# Escorna_CPU_2_40.net
KiCad netlist of a schematic drawn in EAGLE
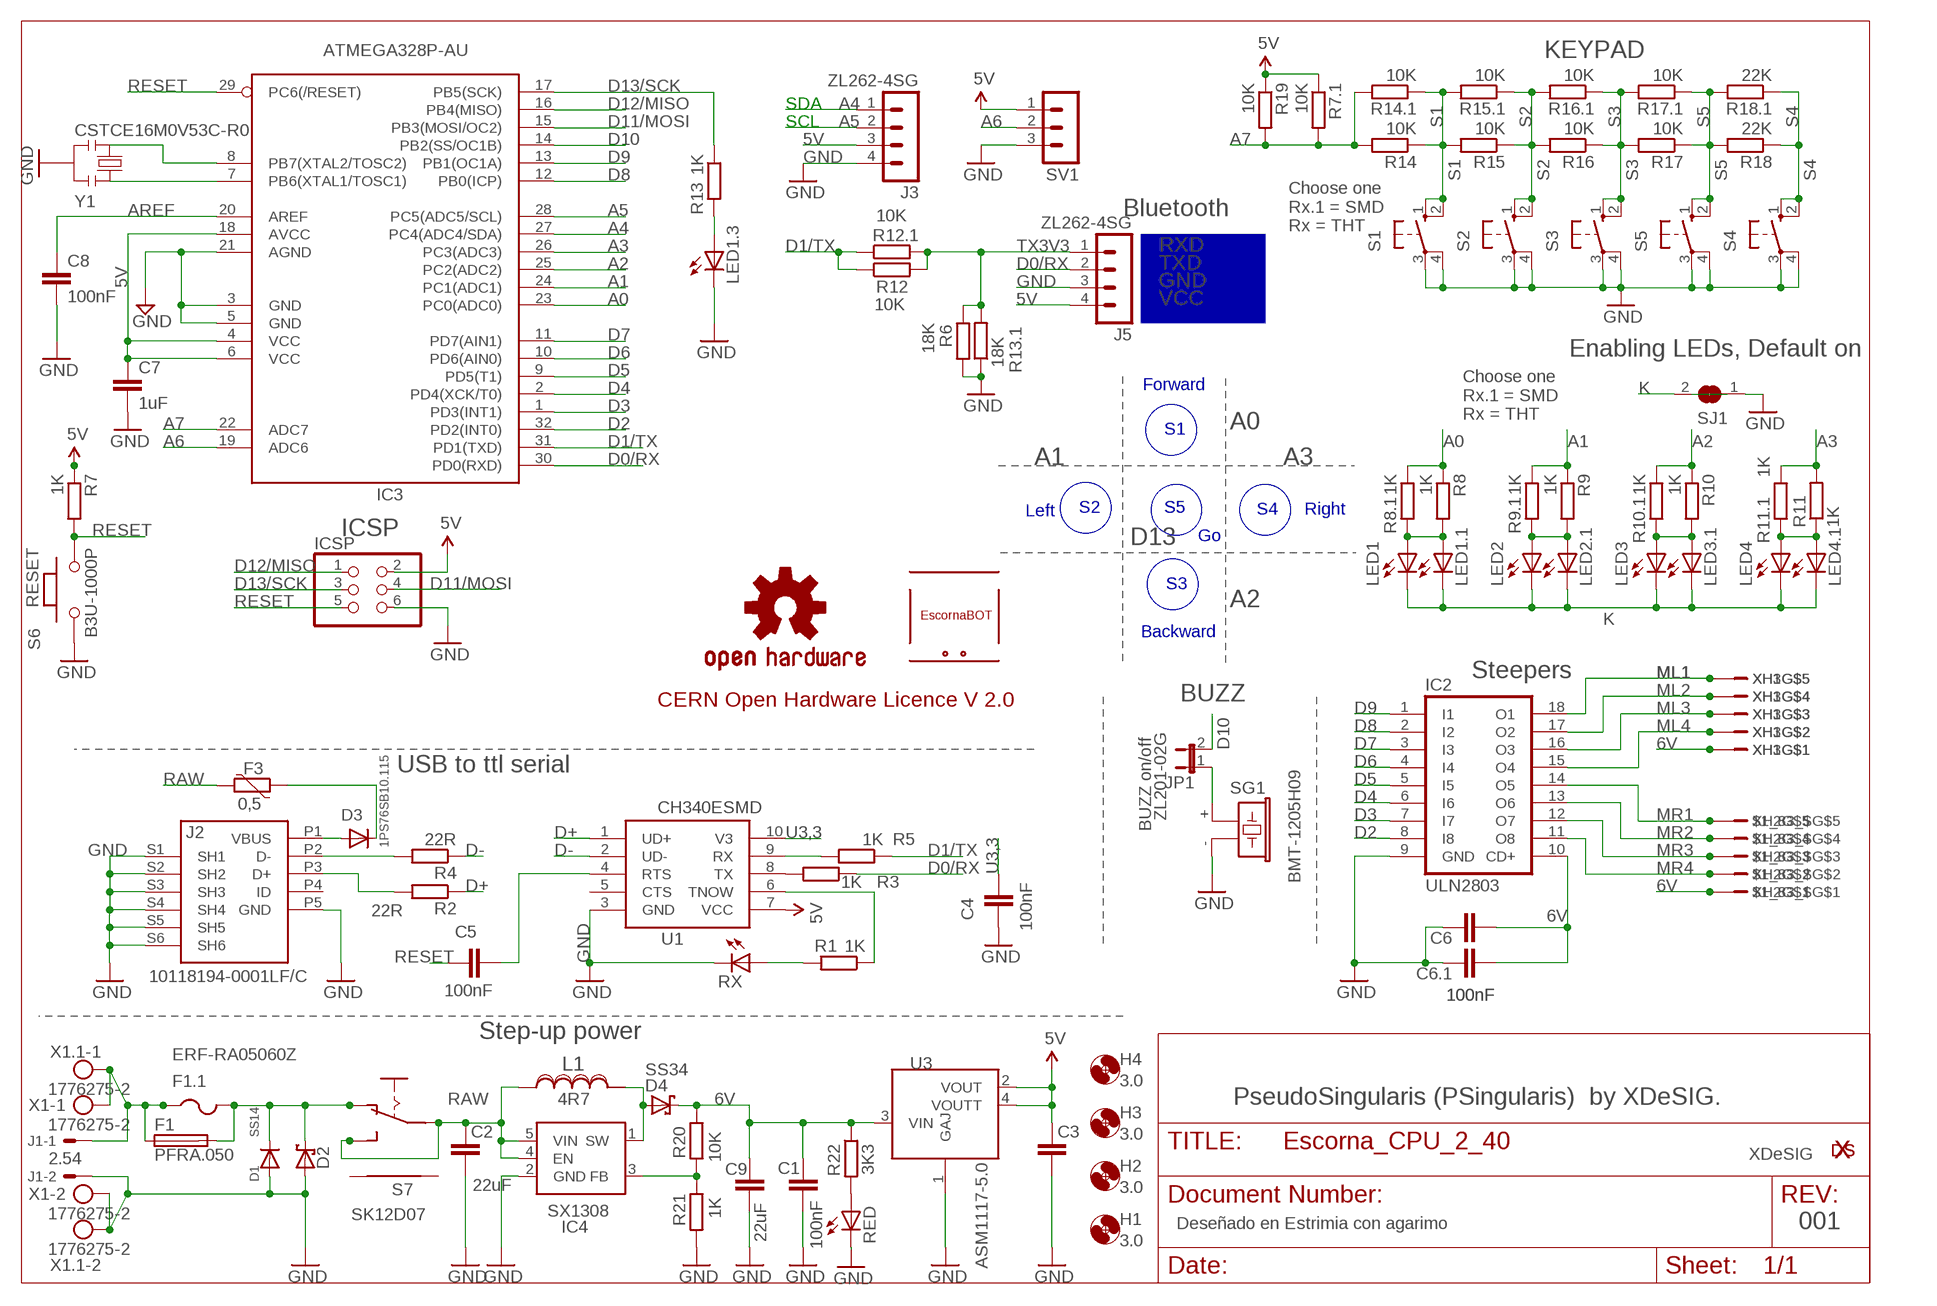
[diagram p0: schematic, sheet 1]

(export (version "E")
  (design (tool "Eeschema 10.0.6"))
  (components
    (comp (ref "$1_82_$")
      (value "XDESIG_XDESIG21")
      (footprint "eagle-import:XDESIG_XDESIG")
      (libsource (lib "eagle-import") (part "XDESIG_XDESIG21"))
    )
    (comp (ref "$1_83_$")
      (value "B5B-XH-A")
      (footprint "eagle-import:B5B-XH-A")
      (libsource (lib "eagle-import") (part "B5B-XH-A"))
    )
    (comp (ref "C1")
      (value "100nF")
      (footprint "eagle-import:C0603-ROUND")
      (fields (field (name "PART_NUMBER") "cl10b104kbnc"))
      (libsource (lib "eagle-import") (part "0015_100NF_0603"))
    )
    (comp (ref "C2")
      (value "22uF")
      (footprint "eagle-import:C1206K")
      (libsource (lib "eagle-import") (part "C-EUC1206K"))
    )
    (comp (ref "C3")
      (value "10uF")
      (footprint "eagle-import:C1206K")
      (libsource (lib "eagle-import") (part "C-EUC1206K"))
    )
    (comp (ref "C4")
      (value "100nF")
      (footprint "eagle-import:C0603-ROUND")
      (fields (field (name "PART_NUMBER") "cl10b104kbnc"))
      (libsource (lib "eagle-import") (part "0015_100NF_0603"))
    )
    (comp (ref "C5")
      (value "100nF")
      (footprint "eagle-import:C0603-ROUND")
      (fields (field (name "PART_NUMBER") "cl10b104kbnc"))
      (libsource (lib "eagle-import") (part "0015_100NF_0603"))
    )
    (comp (ref "C6")
      (value "100nF")
      (footprint "eagle-import:C025-024X044")
      (libsource (lib "eagle-import") (part "C-EU025-024X044"))
    )
    (comp (ref "C6.1")
      (value "100nF")
      (footprint "eagle-import:C0603K")
      (libsource (lib "eagle-import") (part "C-EUC0603K"))
    )
    (comp (ref "C7")
      (value "1uF")
      (footprint "eagle-import:C0603-ROUND")
      (fields (field (name "PART_NUMBER") "1uF_0603/GRM188R61E105KA12D"))
      (libsource (lib "eagle-import") (part "0006_1UF_0603/GRM188R61E105KA12D"))
    )
    (comp (ref "C8")
      (value "100nF")
      (footprint "eagle-import:C0603-ROUND")
      (fields (field (name "PART_NUMBER") "cl10b104kbnc"))
      (libsource (lib "eagle-import") (part "0015_100NF_0603"))
    )
    (comp (ref "C9")
      (value "22uF")
      (footprint "eagle-import:C1206K")
      (libsource (lib "eagle-import") (part "C-EUC1206K"))
    )
    (comp (ref "D1")
      (value "SS14")
      (footprint "eagle-import:SMADIODE")
      (libsource (lib "eagle-import") (part "DIODESMA"))
    )
    (comp (ref "D2")
      (value "1N5817")
      (footprint "eagle-import:DO41-10")
      (libsource (lib "eagle-import") (part "P4KEXX"))
    )
    (comp (ref "D3")
      (value "1PS76SB10.115")
      (footprint "eagle-import:SOD-323F")
      (libsource (lib "eagle-import") (part "DIODESOD-323F"))
    )
    (comp (ref "D4")
      (value "SS34")
      (footprint "eagle-import:DIODE_SMA")
      (libsource (lib "eagle-import") (part "DIODE_SCHOTTKY-DIODESMA"))
    )
    (comp (ref "ESC")
      (value "ESCORNABOT")
      (footprint "eagle-import:ESCORNA_PEQUE")
      (libsource (lib "eagle-import") (part "ESCORNABOT"))
    )
    (comp (ref "F1")
      (value "PFRA.050")
      (footprint "eagle-import:TE5")
      (libsource (lib "eagle-import") (part "FUSETE5"))
    )
    (comp (ref "F1.1")
      (value "ERF-RA05060Z")
      (footprint "eagle-import:R1206")
      (libsource (lib "eagle-import") (part "PTCFUSE-1206"))
    )
    (comp (ref "F3")
      (value "0,5")
      (footprint "eagle-import:R1206")
      (libsource (lib "eagle-import") (part "PTC1206L"))
    )
    (comp (ref "H1")
      (value "3.0")
      (footprint "eagle-import:3,0")
      (libsource (lib "eagle-import") (part "MOUNT-HOLE3.0"))
    )
    (comp (ref "H2")
      (value "3.0")
      (footprint "eagle-import:3,0")
      (libsource (lib "eagle-import") (part "MOUNT-HOLE3.0"))
    )
    (comp (ref "H3")
      (value "3.0")
      (footprint "eagle-import:3,0")
      (libsource (lib "eagle-import") (part "MOUNT-HOLE3.0"))
    )
    (comp (ref "H4")
      (value "3.0")
      (footprint "eagle-import:3,0")
      (libsource (lib "eagle-import") (part "MOUNT-HOLE3.0"))
    )
    (comp (ref "IC2")
      (value "ULN2803")
      (footprint "eagle-import:DIL18")
      (libsource (lib "eagle-import") (part "ULN2803A"))
    )
    (comp (ref "IC3")
      (value "ATMEGA328P-AU")
      (footprint "eagle-import:TQFP32-08")
      (libsource (lib "eagle-import") (part "0265_ATMEGA328P-AU"))
    )
    (comp (ref "IC4")
      (value "SX1308")
      (footprint "eagle-import:SOT23-6")
      (libsource (lib "eagle-import") (part "SX1308"))
    )
    (comp (ref "ICSP")
      (value "0114_PH254-203DF118A00V")
      (footprint "eagle-import:2X03")
      (fields (field (name "PART_NUMBER") "PH254-203DF118A00V"))
      (libsource (lib "eagle-import") (part "0114_PH254-203DF118A00V"))
    )
    (comp (ref "J1")
      (value "2.54")
      (footprint "eagle-import:6410-02")
      (libsource (lib "eagle-import") (part "22-?-0227-2021"))
    )
    (comp (ref "J2")
      (value "10118194-0001LF/C")
      (footprint "eagle-import:SMARTPRJ_CON2_USB_MICRO_B_AT")
      (libsource (lib "eagle-import") (part "SMARTPRJ_MYCON2_USB-MINI-B"))
    )
    (comp (ref "J3")
      (value "ZL262-4SG")
      (footprint "eagle-import:MA04-1")
      (libsource (lib "eagle-import") (part "MA04-1"))
    )
    (comp (ref "J5")
      (value "ZL262-4SG")
      (footprint "eagle-import:MA04-1")
      (libsource (lib "eagle-import") (part "MA04-1"))
    )
    (comp (ref "JP1")
      (value "ZL201-02G")
      (footprint "eagle-import:JP1")
      (libsource (lib "eagle-import") (part "JP1E"))
    )
    (comp (ref "L1")
      (value "4R7")
      (footprint "eagle-import:SRN6045")
      (fields (field (name "MF") "Bourns") (field (name "MP") "SRN6045-330M"))
      (libsource (lib "eagle-import") (part "SRN6045-330M6045"))
    )
    (comp (ref "LED1")
      (value "LED3MM")
      (footprint "eagle-import:LED3MM")
      (libsource (lib "eagle-import") (part "LED3MM"))
    )
    (comp (ref "LED1.1")
      (value "LEDCHIPLED_0603")
      (footprint "eagle-import:CHIPLED_0603")
      (libsource (lib "eagle-import") (part "LEDCHIPLED_0603"))
    )
    (comp (ref "LED1.3")
      (value "LEDCHIPLED_0603")
      (footprint "eagle-import:CHIPLED_0603")
      (libsource (lib "eagle-import") (part "LEDCHIPLED_0603"))
    )
    (comp (ref "LED2")
      (value "LED3MM")
      (footprint "eagle-import:LED3MM")
      (libsource (lib "eagle-import") (part "LED3MM"))
    )
    (comp (ref "LED2.1")
      (value "LEDCHIPLED_0603")
      (footprint "eagle-import:CHIPLED_0603")
      (libsource (lib "eagle-import") (part "LEDCHIPLED_0603"))
    )
    (comp (ref "LED3")
      (value "LED3MM")
      (footprint "eagle-import:LED3MM")
      (libsource (lib "eagle-import") (part "LED3MM"))
    )
    (comp (ref "LED3.1")
      (value "LEDCHIPLED_0603")
      (footprint "eagle-import:CHIPLED_0603")
      (libsource (lib "eagle-import") (part "LEDCHIPLED_0603"))
    )
    (comp (ref "LED4")
      (value "LED3MM")
      (footprint "eagle-import:LED3MM")
      (libsource (lib "eagle-import") (part "LED3MM"))
    )
    (comp (ref "LED4.1")
      (value "LEDCHIPLED_0603")
      (footprint "eagle-import:CHIPLED_0603")
      (libsource (lib "eagle-import") (part "LEDCHIPLED_0603"))
    )
    (comp (ref "LOGO2")
      (value "OSHW-LOGOL")
      (footprint "eagle-import:ESCORNA_LBRESCORNA_CPU_2_10_SPARKFUN-AESTHETICS_OSHW-LOGO-L")
      (libsource (lib "eagle-import") (part "OSHW-LOGOL"))
    )
    (comp (ref "R1")
      (value "1K")
      (footprint "eagle-import:R0603")
      (libsource (lib "eagle-import") (part "R-EU_R0603"))
    )
    (comp (ref "R2")
      (value "22R")
      (footprint "eagle-import:R0603")
      (libsource (lib "eagle-import") (part "R-EU_R0603"))
    )
    (comp (ref "R3")
      (value "1K")
      (footprint "eagle-import:R0603")
      (libsource (lib "eagle-import") (part "R-EU_R0603"))
    )
    (comp (ref "R4")
      (value "22R")
      (footprint "eagle-import:R0603")
      (libsource (lib "eagle-import") (part "R-EU_R0603"))
    )
    (comp (ref "R5")
      (value "1K")
      (footprint "eagle-import:R0603")
      (libsource (lib "eagle-import") (part "R-EU_R0603"))
    )
    (comp (ref "R6")
      (value "18K")
      (footprint "eagle-import:0204_7")
      (libsource (lib "eagle-import") (part "R-EU_0204/7"))
    )
    (comp (ref "R7")
      (value "1K")
      (footprint "eagle-import:R0603")
      (libsource (lib "eagle-import") (part "R-EU_R0603"))
    )
    (comp (ref "R7.1")
      (value "10K")
      (footprint "eagle-import:R0603")
      (libsource (lib "eagle-import") (part "R-EU_R0603"))
    )
    (comp (ref "R8")
      (value "1K")
      (footprint "eagle-import:0204_7")
      (libsource (lib "eagle-import") (part "R-EU_0204/7"))
    )
    (comp (ref "R8.1")
      (value "1K")
      (footprint "eagle-import:R0603")
      (libsource (lib "eagle-import") (part "R-EU_R0603"))
    )
    (comp (ref "R9")
      (value "1K")
      (footprint "eagle-import:0204_7")
      (libsource (lib "eagle-import") (part "R-EU_0204/7"))
    )
    (comp (ref "R9.1")
      (value "1K")
      (footprint "eagle-import:R0603")
      (libsource (lib "eagle-import") (part "R-EU_R0603"))
    )
    (comp (ref "R10")
      (value "1K")
      (footprint "eagle-import:0204_7")
      (libsource (lib "eagle-import") (part "R-EU_0204/7"))
    )
    (comp (ref "R10.1")
      (value "1K")
      (footprint "eagle-import:R0603")
      (libsource (lib "eagle-import") (part "R-EU_R0603"))
    )
    (comp (ref "R11")
      (value "1K")
      (footprint "eagle-import:0204_7")
      (libsource (lib "eagle-import") (part "R-EU_0204/7"))
    )
    (comp (ref "R11.1")
      (value "1K")
      (footprint "eagle-import:R0603")
      (libsource (lib "eagle-import") (part "R-EU_R0603"))
    )
    (comp (ref "R12")
      (value "10K")
      (footprint "eagle-import:0204_7")
      (libsource (lib "eagle-import") (part "R-EU_0204/7"))
    )
    (comp (ref "R12.1")
      (value "10K")
      (footprint "eagle-import:R0603")
      (libsource (lib "eagle-import") (part "R-EU_R0603"))
    )
    (comp (ref "R13")
      (value "1K")
      (footprint "eagle-import:R0603")
      (libsource (lib "eagle-import") (part "R-EU_R0603"))
    )
    (comp (ref "R13.1")
      (value "18K")
      (footprint "eagle-import:R0603")
      (libsource (lib "eagle-import") (part "R-EU_R0603"))
    )
    (comp (ref "R14")
      (value "10K")
      (footprint "eagle-import:0204_7")
      (libsource (lib "eagle-import") (part "R-EU_0204/7"))
    )
    (comp (ref "R14.1")
      (value "10K")
      (footprint "eagle-import:R0603")
      (libsource (lib "eagle-import") (part "R-EU_R0603"))
    )
    (comp (ref "R15")
      (value "10K")
      (footprint "eagle-import:0204_7")
      (libsource (lib "eagle-import") (part "R-EU_0204/7"))
    )
    (comp (ref "R15.1")
      (value "10K")
      (footprint "eagle-import:R0603")
      (libsource (lib "eagle-import") (part "R-EU_R0603"))
    )
    (comp (ref "R16")
      (value "10K")
      (footprint "eagle-import:0204_7")
      (libsource (lib "eagle-import") (part "R-EU_0204/7"))
    )
    (comp (ref "R16.1")
      (value "10K")
      (footprint "eagle-import:R0603")
      (libsource (lib "eagle-import") (part "R-EU_R0603"))
    )
    (comp (ref "R17")
      (value "10K")
      (footprint "eagle-import:0204_7")
      (libsource (lib "eagle-import") (part "R-EU_0204/7"))
    )
    (comp (ref "R17.1")
      (value "10K")
      (footprint "eagle-import:R0603")
      (libsource (lib "eagle-import") (part "R-EU_R0603"))
    )
    (comp (ref "R18")
      (value "22K")
      (footprint "eagle-import:0204_7")
      (libsource (lib "eagle-import") (part "R-EU_0204/7"))
    )
    (comp (ref "R18.1")
      (value "22K")
      (footprint "eagle-import:R0603")
      (libsource (lib "eagle-import") (part "R-EU_R0603"))
    )
    (comp (ref "R19")
      (value "10K")
      (footprint "eagle-import:0204_7")
      (libsource (lib "eagle-import") (part "R-EU_0204/7"))
    )
    (comp (ref "R20")
      (value "10K")
      (footprint "eagle-import:R0603")
      (libsource (lib "eagle-import") (part "R-EU_R0603"))
    )
    (comp (ref "R21")
      (value "1K")
      (footprint "eagle-import:R0603")
      (libsource (lib "eagle-import") (part "R-EU_R0603"))
    )
    (comp (ref "R22")
      (value "3K3")
      (footprint "eagle-import:R0603")
      (libsource (lib "eagle-import") (part "R-EU_R0603"))
    )
    (comp (ref "RED")
      (value "LEDCHIPLED_0603")
      (footprint "eagle-import:CHIPLED_0603")
      (libsource (lib "eagle-import") (part "LEDCHIPLED_0603"))
    )
    (comp (ref "RX")
      (value "LEDCHIPLED_0603")
      (footprint "eagle-import:CHIPLED_0603")
      (libsource (lib "eagle-import") (part "LEDCHIPLED_0603"))
    )
    (comp (ref "S1")
      (value "40-XX")
      (footprint "eagle-import:B3F-40")
      (fields (field (name "MF") "OMRON COMPONENTS USA") (field (name "MPN") "B3F-4000"))
      (libsource (lib "eagle-import") (part "40-XX"))
    )
    (comp (ref "S2")
      (value "40-XX")
      (footprint "eagle-import:B3F-40")
      (fields (field (name "MF") "OMRON COMPONENTS USA") (field (name "MPN") "B3F-4000"))
      (libsource (lib "eagle-import") (part "40-XX"))
    )
    (comp (ref "S3")
      (value "40-XX")
      (footprint "eagle-import:B3F-40")
      (fields (field (name "MF") "OMRON COMPONENTS USA") (field (name "MPN") "B3F-4000"))
      (libsource (lib "eagle-import") (part "40-XX"))
    )
    (comp (ref "S4")
      (value "40-XX")
      (footprint "eagle-import:B3F-40")
      (fields (field (name "MF") "OMRON COMPONENTS USA") (field (name "MPN") "B3F-4000"))
      (libsource (lib "eagle-import") (part "40-XX"))
    )
    (comp (ref "S5")
      (value "40-XX")
      (footprint "eagle-import:B3F-40")
      (fields (field (name "MF") "OMRON COMPONENTS USA") (field (name "MPN") "B3F-4000"))
      (libsource (lib "eagle-import") (part "40-XX"))
    )
    (comp (ref "S6")
      (value "B3U-1000P")
      (footprint "eagle-import:SMD_157SW")
      (fields (field (name "PART_NUMBER") "IT-1185AP1C-160G-G_T&R"))
      (libsource (lib "eagle-import") (part "0173_IT-1185AP1C-160G-G_T&R"))
    )
    (comp (ref "S7")
      (value "SK12D07")
      (footprint "eagle-import:ESCORNA_SK-12D07")
      (libsource (lib "eagle-import") (part "ESCORNA_SK12F14D"))
    )
    (comp (ref "SG1")
      (value "BMT-1205H09")
      (footprint "eagle-import:F_CM12P")
      (libsource (lib "eagle-import") (part "F/CM12P"))
    )
    (comp (ref "SJ1") (value "SJ") (footprint "eagle-import:SJ") (libsource (lib "eagle-import") (part "SJ")))
    (comp (ref "SV1")
      (value "MA03-1")
      (footprint "eagle-import:MA03-1")
      (libsource (lib "eagle-import") (part "MA03-1"))
    )
    (comp (ref "U1")
      (value "CH340ESMD")
      (footprint "eagle-import:MSOP10")
      (fields (field (name "MF") "WCH") (field (name "MP") "CH340E"))
      (libsource (lib "eagle-import") (part "CH340ESMD"))
    )
    (comp (ref "U3")
      (value "ASM1117-5.0")
      (footprint "eagle-import:SOT223")
      (libsource (lib "eagle-import") (part "ASM1117-3.3"))
    )
    (comp (ref "X1")
      (value "1776275-2")
      (footprint "eagle-import:AK550_2")
      (libsource (lib "eagle-import") (part "AK550/2"))
    )
    (comp (ref "X1.1")
      (value "1776275-2")
      (footprint "eagle-import:AK550_2")
      (fields (field (name "OC_FARNELL") "unknown") (field (name "OC_NEWARK") "unknown"))
      (libsource (lib "eagle-import") (part "AK550/2"))
    )
    (comp (ref "XDS2")
      (value "XDESIG")
      (footprint "eagle-import:XDESIG_CU_2")
      (libsource (lib "eagle-import") (part "XDESIG"))
    )
    (comp (ref "XH1")
      (value "B5B-XH-A")
      (footprint "eagle-import:B5B-XH-A")
      (libsource (lib "eagle-import") (part "B5B-XH-A"))
    )
    (comp (ref "XH2")
      (value "B5B-XH-A")
      (footprint "eagle-import:B5B-XH-A")
      (libsource (lib "eagle-import") (part "B5B-XH-A"))
    )
    (comp (ref "XH3")
      (value "B5B-XH-A")
      (footprint "eagle-import:B5B-XH-A")
      (libsource (lib "eagle-import") (part "B5B-XH-A"))
    )
    (comp (ref "Y1")
      (value "CSTCE16M0V53C-R0")
      (footprint "eagle-import:RESONATOR")
      (fields (field (name "PART_NUMBER") "CSTCE16M0V53-R0"))
      (libsource (lib "eagle-import") (part "0011_CSTCE16M0V53-R0"))
    )
  )
  (nets
    (net (code "1") (name "/6V") (class "Default")
      (node (ref "$1_83_$") (pin "P$1") (pinfunction "1_P$1") (pintype "passive"))
      (node (ref "C1") (pin "2") (pinfunction "2_2") (pintype "passive"))
      (node (ref "C6") (pin "2") (pinfunction "2_2") (pintype "passive"))
      (node (ref "C6.1") (pin "2") (pinfunction "2_2") (pintype "passive"))
      (node (ref "C9") (pin "2") (pinfunction "2_2") (pintype "passive"))
      (node (ref "D4") (pin "C") (pinfunction "C_C") (pintype "passive"))
      (node (ref "IC2") (pin "10") (pinfunction "CD+_10") (pintype "passive"))
      (node (ref "R20") (pin "1") (pinfunction "1_1") (pintype "passive"))
      (node (ref "R22") (pin "1") (pinfunction "1_1") (pintype "passive"))
      (node (ref "U3") (pin "3") (pinfunction "VIN_3") (pintype "bidirectional"))
      (node (ref "XH1") (pin "P$1") (pinfunction "1_P$1") (pintype "passive"))
      (node (ref "XH2") (pin "P$1") (pinfunction "1_P$1") (pintype "passive"))
      (node (ref "XH3") (pin "P$1") (pinfunction "1_P$1") (pintype "passive"))
    )
    (net (code "2") (name "/A0") (class "Default")
      (node (ref "IC3") (pin "23") (pinfunction "PC0(ADC0)_23") (pintype "bidirectional"))
      (node (ref "R8") (pin "1") (pinfunction "1_1") (pintype "passive"))
      (node (ref "R8.1") (pin "1") (pinfunction "1_1") (pintype "passive"))
    )
    (net (code "3") (name "/A1") (class "Default")
      (node (ref "IC3") (pin "24") (pinfunction "PC1(ADC1)_24") (pintype "bidirectional"))
      (node (ref "R9") (pin "1") (pinfunction "1_1") (pintype "passive"))
      (node (ref "R9.1") (pin "1") (pinfunction "1_1") (pintype "passive"))
    )
    (net (code "4") (name "/A2") (class "Default")
      (node (ref "IC3") (pin "25") (pinfunction "PC2(ADC2)_25") (pintype "bidirectional"))
      (node (ref "R10") (pin "1") (pinfunction "1_1") (pintype "passive"))
      (node (ref "R10.1") (pin "1") (pinfunction "1_1") (pintype "passive"))
    )
    (net (code "5") (name "/A3") (class "Default")
      (node (ref "IC3") (pin "26") (pinfunction "PC3(ADC3)_26") (pintype "bidirectional"))
      (node (ref "R11") (pin "2") (pinfunction "2_2") (pintype "passive"))
      (node (ref "R11.1") (pin "1") (pinfunction "1_1") (pintype "passive"))
    )
    (net (code "6") (name "/A4") (class "Default")
      (node (ref "IC3") (pin "27") (pinfunction "PC4(ADC4/SDA)_27") (pintype "bidirectional"))
      (node (ref "J3") (pin "1") (pinfunction "1_1") (pintype "passive"))
    )
    (net (code "7") (name "/A5") (class "Default")
      (node (ref "IC3") (pin "28") (pinfunction "PC5(ADC5/SCL)_28") (pintype "bidirectional"))
      (node (ref "J3") (pin "2") (pinfunction "2_2") (pintype "passive"))
    )
    (net (code "8") (name "/A6") (class "Default")
      (node (ref "IC3") (pin "19") (pinfunction "ADC6_19") (pintype "bidirectional"))
      (node (ref "SV1") (pin "2") (pinfunction "2_2") (pintype "passive"))
    )
    (net (code "9") (name "/A7") (class "Default")
      (node (ref "IC3") (pin "22") (pinfunction "ADC7_22") (pintype "bidirectional"))
      (node (ref "R14") (pin "2") (pinfunction "2_2") (pintype "passive"))
      (node (ref "R14.1") (pin "2") (pinfunction "2_2") (pintype "passive"))
      (node (ref "R19") (pin "2") (pinfunction "2_2") (pintype "passive"))
      (node (ref "R7.1") (pin "2") (pinfunction "2_2") (pintype "passive"))
    )
    (net (code "10") (name "/AREF") (class "Default")
      (node (ref "C8") (pin "1") (pinfunction "1_1") (pintype "passive"))
      (node (ref "IC3") (pin "20") (pinfunction "AREF_20") (pintype "bidirectional"))
    )
    (net (code "11") (name "/D+") (class "Default")
      (node (ref "R2") (pin "1") (pinfunction "1_1") (pintype "passive"))
      (node (ref "U1") (pin "1") (pinfunction "UD+_1") (pintype "bidirectional"))
    )
    (net (code "12") (name "/D-") (class "Default")
      (node (ref "R4") (pin "1") (pinfunction "1_1") (pintype "passive"))
      (node (ref "U1") (pin "2") (pinfunction "UD-_2") (pintype "bidirectional"))
    )
    (net (code "13") (name "/D0{slash}RX") (class "Default")
      (node (ref "IC3") (pin "30") (pinfunction "PD0(RXD)_30") (pintype "bidirectional"))
      (node (ref "J5") (pin "2") (pinfunction "2_2") (pintype "passive"))
      (node (ref "R3") (pin "1") (pinfunction "1_1") (pintype "passive"))
    )
    (net (code "14") (name "/D1{slash}TX") (class "Default")
      (node (ref "IC3") (pin "31") (pinfunction "PD1(TXD)_31") (pintype "bidirectional"))
      (node (ref "R12") (pin "1") (pinfunction "1_1") (pintype "passive"))
      (node (ref "R12.1") (pin "1") (pinfunction "1_1") (pintype "passive"))
      (node (ref "R5") (pin "1") (pinfunction "1_1") (pintype "passive"))
    )
    (net (code "15") (name "/D2") (class "Default")
      (node (ref "IC2") (pin "8") (pinfunction "I8_8") (pintype "input"))
      (node (ref "IC3") (pin "32") (pinfunction "PD2(INT0)_32") (pintype "bidirectional"))
    )
    (net (code "16") (name "/D3") (class "Default")
      (node (ref "IC2") (pin "7") (pinfunction "I7_7") (pintype "input"))
      (node (ref "IC3") (pin "1") (pinfunction "PD3(INT1)_1") (pintype "bidirectional"))
    )
    (net (code "17") (name "/D4") (class "Default")
      (node (ref "IC2") (pin "6") (pinfunction "I6_6") (pintype "input"))
      (node (ref "IC3") (pin "2") (pinfunction "PD4(XCK/T0)_2") (pintype "bidirectional"))
    )
    (net (code "18") (name "/D5") (class "Default")
      (node (ref "IC2") (pin "5") (pinfunction "I5_5") (pintype "input"))
      (node (ref "IC3") (pin "9") (pinfunction "PD5(T1)_9") (pintype "bidirectional"))
    )
    (net (code "19") (name "/D6") (class "Default")
      (node (ref "IC2") (pin "4") (pinfunction "I4_4") (pintype "input"))
      (node (ref "IC3") (pin "10") (pinfunction "PD6(AIN0)_10") (pintype "bidirectional"))
    )
    (net (code "20") (name "/D7") (class "Default")
      (node (ref "IC2") (pin "3") (pinfunction "I3_3") (pintype "input"))
      (node (ref "IC3") (pin "11") (pinfunction "PD7(AIN1)_11") (pintype "bidirectional"))
    )
    (net (code "21") (name "/D8") (class "Default")
      (node (ref "IC2") (pin "2") (pinfunction "I2_2") (pintype "input"))
      (node (ref "IC3") (pin "12") (pinfunction "PB0(ICP)_12") (pintype "bidirectional"))
    )
    (net (code "22") (name "/D9") (class "Default")
      (node (ref "IC2") (pin "1") (pinfunction "I1_1") (pintype "input"))
      (node (ref "IC3") (pin "13") (pinfunction "PB1(OC1A)_13") (pintype "bidirectional"))
    )
    (net (code "23") (name "/D10") (class "Default")
      (node (ref "IC3") (pin "14") (pinfunction "PB2(SS/OC1B)_14") (pintype "bidirectional"))
      (node (ref "JP1") (pin "2") (pinfunction "2_2") (pintype "passive"))
    )
    (net (code "24") (name "/D11{slash}MOSI") (class "Default")
      (node (ref "IC3") (pin "15") (pinfunction "PB3(MOSI/OC2)_15") (pintype "bidirectional"))
      (node (ref "ICSP") (pin "4") (pinfunction "4_4") (pintype "passive"))
    )
    (net (code "25") (name "/D12{slash}MISO") (class "Default")
      (node (ref "IC3") (pin "16") (pinfunction "PB4(MISO)_16") (pintype "bidirectional"))
      (node (ref "ICSP") (pin "1") (pinfunction "1_1") (pintype "passive"))
    )
    (net (code "26") (name "/D13{slash}SCK") (class "Default")
      (node (ref "IC3") (pin "17") (pinfunction "PB5(SCK)_17") (pintype "bidirectional"))
      (node (ref "ICSP") (pin "3") (pinfunction "3_3") (pintype "passive"))
      (node (ref "R13") (pin "1") (pinfunction "1_1") (pintype "passive"))
    )
    (net (code "27") (name "/K") (class "Default")
      (node (ref "LED1") (pin "K") (pinfunction "C_K") (pintype "passive"))
      (node (ref "LED1.1") (pin "C") (pinfunction "C_C") (pintype "passive"))
      (node (ref "LED2") (pin "K") (pinfunction "C_K") (pintype "passive"))
      (node (ref "LED2.1") (pin "C") (pinfunction "C_C") (pintype "passive"))
      (node (ref "LED3") (pin "K") (pinfunction "C_K") (pintype "passive"))
      (node (ref "LED3.1") (pin "C") (pinfunction "C_C") (pintype "passive"))
      (node (ref "LED4") (pin "K") (pinfunction "C_K") (pintype "passive"))
      (node (ref "LED4.1") (pin "C") (pinfunction "C_C") (pintype "passive"))
      (node (ref "SJ1") (pin "2") (pinfunction "2_2") (pintype "passive"))
    )
    (net (code "28") (name "/ML1") (class "Default")
      (node (ref "IC2") (pin "18") (pinfunction "O1_18") (pintype "open_collector"))
      (node (ref "XH1") (pin "P$5") (pinfunction "1_P$5") (pintype "passive"))
      (node (ref "XH3") (pin "P$5") (pinfunction "1_P$5") (pintype "passive"))
    )
    (net (code "29") (name "/ML2") (class "Default")
      (node (ref "IC2") (pin "17") (pinfunction "O2_17") (pintype "open_collector"))
      (node (ref "XH1") (pin "P$4") (pinfunction "1_P$4") (pintype "passive"))
      (node (ref "XH3") (pin "P$4") (pinfunction "1_P$4") (pintype "passive"))
    )
    (net (code "30") (name "/ML3") (class "Default")
      (node (ref "IC2") (pin "16") (pinfunction "O3_16") (pintype "open_collector"))
      (node (ref "XH1") (pin "P$3") (pinfunction "1_P$3") (pintype "passive"))
      (node (ref "XH3") (pin "P$3") (pinfunction "1_P$3") (pintype "passive"))
    )
    (net (code "31") (name "/ML4") (class "Default")
      (node (ref "IC2") (pin "15") (pinfunction "O4_15") (pintype "open_collector"))
      (node (ref "XH1") (pin "P$2") (pinfunction "1_P$2") (pintype "passive"))
      (node (ref "XH3") (pin "P$2") (pinfunction "1_P$2") (pintype "passive"))
    )
    (net (code "32") (name "/MR1") (class "Default")
      (node (ref "$1_83_$") (pin "P$5") (pinfunction "1_P$5") (pintype "passive"))
      (node (ref "IC2") (pin "14") (pinfunction "O5_14") (pintype "open_collector"))
      (node (ref "XH2") (pin "P$5") (pinfunction "1_P$5") (pintype "passive"))
    )
    (net (code "33") (name "/MR2") (class "Default")
      (node (ref "$1_83_$") (pin "P$4") (pinfunction "1_P$4") (pintype "passive"))
      (node (ref "IC2") (pin "13") (pinfunction "O6_13") (pintype "open_collector"))
      (node (ref "XH2") (pin "P$4") (pinfunction "1_P$4") (pintype "passive"))
    )
    (net (code "34") (name "/MR3") (class "Default")
      (node (ref "$1_83_$") (pin "P$3") (pinfunction "1_P$3") (pintype "passive"))
      (node (ref "IC2") (pin "12") (pinfunction "O7_12") (pintype "open_collector"))
      (node (ref "XH2") (pin "P$3") (pinfunction "1_P$3") (pintype "passive"))
    )
    (net (code "35") (name "/MR4") (class "Default")
      (node (ref "$1_83_$") (pin "P$2") (pinfunction "1_P$2") (pintype "passive"))
      (node (ref "IC2") (pin "11") (pinfunction "O8_11") (pintype "open_collector"))
      (node (ref "XH2") (pin "P$2") (pinfunction "1_P$2") (pintype "passive"))
    )
    (net (code "36") (name "/RAW") (class "Default")
      (node (ref "C2") (pin "2") (pinfunction "2_2") (pintype "passive"))
      (node (ref "F3") (pin "2") (pinfunction "2_2") (pintype "passive"))
      (node (ref "IC4") (pin "4") (pinfunction "EN_4") (pintype "bidirectional"))
      (node (ref "IC4") (pin "5") (pinfunction "VIN_5") (pintype "bidirectional"))
      (node (ref "L1") (pin "2") (pinfunction "2_2") (pintype "passive"))
      (node (ref "S7") (pin "P$1") (pinfunction "P_P$1") (pintype "passive"))
      (node (ref "S7") (pin "P$3") (pinfunction "S_P$3") (pintype "passive"))
    )
    (net (code "37") (name "/RESET") (class "Default")
      (node (ref "C5") (pin "1") (pinfunction "1_1") (pintype "passive"))
      (node (ref "IC3") (pin "29") (pinfunction "PC6(/RESET)_29") (pintype "bidirectional"))
      (node (ref "ICSP") (pin "5") (pinfunction "5_5") (pintype "passive"))
      (node (ref "R7") (pin "2") (pinfunction "2_2") (pintype "passive"))
      (node (ref "S6") (pin "2") (pinfunction "2_2") (pintype "passive"))
    )
    (net (code "38") (name "/S1") (class "Default")
      (node (ref "R14") (pin "1") (pinfunction "1_1") (pintype "passive"))
      (node (ref "R14.1") (pin "1") (pinfunction "1_1") (pintype "passive"))
      (node (ref "R15") (pin "2") (pinfunction "2_2") (pintype "passive"))
      (node (ref "R15.1") (pin "2") (pinfunction "2_2") (pintype "passive"))
      (node (ref "S1") (pin "1") (pinfunction "S_1") (pintype "passive"))
      (node (ref "S1") (pin "2") (pinfunction "S1_2") (pintype "passive"))
    )
    (net (code "39") (name "/S2") (class "Default")
      (node (ref "R15") (pin "1") (pinfunction "1_1") (pintype "passive"))
      (node (ref "R15.1") (pin "1") (pinfunction "1_1") (pintype "passive"))
      (node (ref "R16") (pin "2") (pinfunction "2_2") (pintype "passive"))
      (node (ref "R16.1") (pin "2") (pinfunction "2_2") (pintype "passive"))
      (node (ref "S2") (pin "1") (pinfunction "S_1") (pintype "passive"))
      (node (ref "S2") (pin "2") (pinfunction "S1_2") (pintype "passive"))
    )
    (net (code "40") (name "/S3") (class "Default")
      (node (ref "R16") (pin "1") (pinfunction "1_1") (pintype "passive"))
      (node (ref "R16.1") (pin "1") (pinfunction "1_1") (pintype "passive"))
      (node (ref "R17") (pin "2") (pinfunction "2_2") (pintype "passive"))
      (node (ref "R17.1") (pin "2") (pinfunction "2_2") (pintype "passive"))
      (node (ref "S3") (pin "1") (pinfunction "S_1") (pintype "passive"))
      (node (ref "S3") (pin "2") (pinfunction "S1_2") (pintype "passive"))
    )
    (net (code "41") (name "/S4") (class "Default")
      (node (ref "R18") (pin "1") (pinfunction "1_1") (pintype "passive"))
      (node (ref "R18.1") (pin "1") (pinfunction "1_1") (pintype "passive"))
      (node (ref "S4") (pin "1") (pinfunction "S_1") (pintype "passive"))
      (node (ref "S4") (pin "2") (pinfunction "S1_2") (pintype "passive"))
    )
    (net (code "42") (name "/S5") (class "Default")
      (node (ref "R17") (pin "1") (pinfunction "1_1") (pintype "passive"))
      (node (ref "R17.1") (pin "1") (pinfunction "1_1") (pintype "passive"))
      (node (ref "R18") (pin "2") (pinfunction "2_2") (pintype "passive"))
      (node (ref "R18.1") (pin "2") (pinfunction "2_2") (pintype "passive"))
      (node (ref "S5") (pin "1") (pinfunction "S_1") (pintype "passive"))
      (node (ref "S5") (pin "2") (pinfunction "S1_2") (pintype "passive"))
    )
    (net (code "43") (name "/TX3V3") (class "Default")
      (node (ref "J5") (pin "1") (pinfunction "1_1") (pintype "passive"))
      (node (ref "R12") (pin "2") (pinfunction "2_2") (pintype "passive"))
      (node (ref "R12.1") (pin "2") (pinfunction "2_2") (pintype "passive"))
      (node (ref "R13.1") (pin "2") (pinfunction "2_2") (pintype "passive"))
      (node (ref "R6") (pin "1") (pinfunction "1_1") (pintype "passive"))
    )
    (net (code "44") (name "/U3,3") (class "Default")
      (node (ref "C4") (pin "2") (pinfunction "2_2") (pintype "passive"))
      (node (ref "U1") (pin "10") (pinfunction "V3_10") (pintype "power_in"))
    )
    (net (code "45") (name "5V") (class "Default")
      (node (ref "C3") (pin "2") (pinfunction "2_2") (pintype "passive"))
      (node (ref "C7") (pin "1") (pinfunction "1_1") (pintype "passive"))
      (node (ref "IC3") (pin "18") (pinfunction "AVCC_18") (pintype "bidirectional"))
      (node (ref "IC3") (pin "4") (pinfunction "VCC_4") (pintype "bidirectional"))
      (node (ref "IC3") (pin "6") (pinfunction "VCC_6") (pintype "bidirectional"))
      (node (ref "ICSP") (pin "2") (pinfunction "2_2") (pintype "passive"))
      (node (ref "J3") (pin "3") (pinfunction "3_3") (pintype "passive"))
      (node (ref "J5") (pin "4") (pinfunction "4_4") (pintype "passive"))
      (node (ref "R19") (pin "1") (pinfunction "1_1") (pintype "passive"))
      (node (ref "R7") (pin "1") (pinfunction "1_1") (pintype "passive"))
      (node (ref "R7.1") (pin "1") (pinfunction "1_1") (pintype "passive"))
      (node (ref "SV1") (pin "1") (pinfunction "1_1") (pintype "passive"))
      (node (ref "U1") (pin "7") (pinfunction "VCC_7") (pintype "power_in"))
      (node (ref "U3") (pin "2") (pinfunction "VOUT_2") (pintype "bidirectional"))
      (node (ref "U3") (pin "4") (pinfunction "VOUTT_4") (pintype "bidirectional"))
    )
    (net (code "46") (name "GND") (class "Default")
      (node (ref "C1") (pin "1") (pinfunction "1_1") (pintype "passive"))
      (node (ref "C2") (pin "1") (pinfunction "1_1") (pintype "passive"))
      (node (ref "C3") (pin "1") (pinfunction "1_1") (pintype "passive"))
      (node (ref "C4") (pin "1") (pinfunction "1_1") (pintype "passive"))
      (node (ref "C6") (pin "1") (pinfunction "1_1") (pintype "passive"))
      (node (ref "C6.1") (pin "1") (pinfunction "1_1") (pintype "passive"))
      (node (ref "C7") (pin "2") (pinfunction "2_2") (pintype "passive"))
      (node (ref "C8") (pin "2") (pinfunction "2_2") (pintype "passive"))
      (node (ref "C9") (pin "1") (pinfunction "1_1") (pintype "passive"))
      (node (ref "D1") (pin "A") (pinfunction "A_A") (pintype "passive"))
      (node (ref "D2") (pin "A") (pinfunction "A_A") (pintype "passive"))
      (node (ref "IC2") (pin "9") (pinfunction "GND_9") (pintype "power_in"))
      (node (ref "IC3") (pin "21") (pinfunction "AGND_21") (pintype "bidirectional"))
      (node (ref "IC3") (pin "3") (pinfunction "GND_3") (pintype "bidirectional"))
      (node (ref "IC3") (pin "5") (pinfunction "GND_5") (pintype "bidirectional"))
      (node (ref "IC4") (pin "2") (pinfunction "GND_2") (pintype "bidirectional"))
      (node (ref "ICSP") (pin "6") (pinfunction "6_6") (pintype "passive"))
      (node (ref "J1") (pin "2") (pinfunction "S_2") (pintype "passive"))
      (node (ref "J2") (pin "P5") (pinfunction "GND_P5") (pintype "passive"))
      (node (ref "J2") (pin "S1") (pinfunction "SH1_S1") (pintype "passive"))
      (node (ref "J2") (pin "S2") (pinfunction "SH2_S2") (pintype "passive"))
      (node (ref "J2") (pin "S3") (pinfunction "SH3_S3") (pintype "passive"))
      (node (ref "J2") (pin "S4") (pinfunction "SH4_S4") (pintype "passive"))
      (node (ref "J2") (pin "S5") (pinfunction "SH5_S5") (pintype "passive"))
      (node (ref "J2") (pin "S6") (pinfunction "SH6_S6") (pintype "passive"))
      (node (ref "J3") (pin "4") (pinfunction "4_4") (pintype "passive"))
      (node (ref "J5") (pin "3") (pinfunction "3_3") (pintype "passive"))
      (node (ref "LED1.3") (pin "C") (pinfunction "C_C") (pintype "passive"))
      (node (ref "R13.1") (pin "1") (pinfunction "1_1") (pintype "passive"))
      (node (ref "R21") (pin "2") (pinfunction "2_2") (pintype "passive"))
      (node (ref "R6") (pin "2") (pinfunction "2_2") (pintype "passive"))
      (node (ref "RED") (pin "C") (pinfunction "C_C") (pintype "passive"))
      (node (ref "RX") (pin "C") (pinfunction "C_C") (pintype "passive"))
      (node (ref "S1") (pin "3") (pinfunction "P_3") (pintype "passive"))
      (node (ref "S1") (pin "4") (pinfunction "P1_4") (pintype "passive"))
      (node (ref "S2") (pin "3") (pinfunction "P_3") (pintype "passive"))
      (node (ref "S2") (pin "4") (pinfunction "P1_4") (pintype "passive"))
      (node (ref "S3") (pin "3") (pinfunction "P_3") (pintype "passive"))
      (node (ref "S3") (pin "4") (pinfunction "P1_4") (pintype "passive"))
      (node (ref "S4") (pin "3") (pinfunction "P_3") (pintype "passive"))
      (node (ref "S4") (pin "4") (pinfunction "P1_4") (pintype "passive"))
      (node (ref "S5") (pin "3") (pinfunction "P_3") (pintype "passive"))
      (node (ref "S5") (pin "4") (pinfunction "P1_4") (pintype "passive"))
      (node (ref "S6") (pin "1") (pinfunction "1_1") (pintype "passive"))
      (node (ref "SG1") (pin "-") (pinfunction "2_-") (pintype "passive"))
      (node (ref "SJ1") (pin "1") (pinfunction "1_1") (pintype "passive"))
      (node (ref "SV1") (pin "3") (pinfunction "3_3") (pintype "passive"))
      (node (ref "U1") (pin "3") (pinfunction "GND_3") (pintype "power_in"))
      (node (ref "U3") (pin "1") (pinfunction "GAJ_1") (pintype "bidirectional"))
      (node (ref "X1") (pin "2") (pinfunction "KL_2") (pintype "passive"))
      (node (ref "X1.1") (pin "2") (pinfunction "KL_2") (pintype "passive"))
      (node (ref "Y1") (pin "2") (pinfunction "2_2") (pintype "passive"))
    )
    (net (code "47") (name "Net-(D3-PadC)") (class "Default")
      (node (ref "D3") (pin "C") (pinfunction "C_C") (pintype "passive"))
      (node (ref "F3") (pin "1") (pinfunction "1_1") (pintype "passive"))
    )
    (net (code "48") (name "Net-(IC3-PB6(XTAL1{slash}TOSC1))") (class "Default")
      (node (ref "IC3") (pin "7") (pinfunction "PB6(XTAL1/TOSC1)_7") (pintype "bidirectional"))
      (node (ref "Y1") (pin "1") (pinfunction "1_1") (pintype "passive"))
    )
    (net (code "49") (name "Net-(IC3-PB7(XTAL2{slash}TOSC2))") (class "Default")
      (node (ref "IC3") (pin "8") (pinfunction "PB7(XTAL2/TOSC2)_8") (pintype "bidirectional"))
      (node (ref "Y1") (pin "3") (pinfunction "3_3") (pintype "passive"))
    )
    (net (code "50") (name "Net-(IC4-FB)") (class "Default")
      (node (ref "IC4") (pin "3") (pinfunction "FB_3") (pintype "bidirectional"))
      (node (ref "R20") (pin "2") (pinfunction "2_2") (pintype "passive"))
      (node (ref "R21") (pin "1") (pinfunction "1_1") (pintype "passive"))
    )
    (net (code "51") (name "Net-(IC4-SW)") (class "Default")
      (node (ref "D4") (pin "A") (pinfunction "A_A") (pintype "passive"))
      (node (ref "IC4") (pin "1") (pinfunction "SW_1") (pintype "bidirectional"))
      (node (ref "L1") (pin "1") (pinfunction "1_1") (pintype "passive"))
    )
    (net (code "52") (name "Net-(J1A-S)") (class "Default")
      (node (ref "F1") (pin "1") (pinfunction "1_1") (pintype "passive"))
      (node (ref "F1.1") (pin "1") (pinfunction "1_1") (pintype "passive"))
      (node (ref "J1") (pin "1") (pinfunction "S_1") (pintype "passive"))
      (node (ref "X1") (pin "1") (pinfunction "KL_1") (pintype "passive"))
      (node (ref "X1.1") (pin "1") (pinfunction "KL_1") (pintype "passive"))
    )
    (net (code "53") (name "Net-(J2-D+)") (class "Default")
      (node (ref "J2") (pin "P3") (pinfunction "D+_P3") (pintype "bidirectional"))
      (node (ref "R2") (pin "2") (pinfunction "2_2") (pintype "passive"))
    )
    (net (code "54") (name "Net-(J2-D-)") (class "Default")
      (node (ref "J2") (pin "P2") (pinfunction "D-_P2") (pintype "bidirectional"))
      (node (ref "R4") (pin "2") (pinfunction "2_2") (pintype "passive"))
    )
    (net (code "55") (name "Net-(J2-VBUS)") (class "Default")
      (node (ref "D3") (pin "A") (pinfunction "A_A") (pintype "passive"))
      (node (ref "J2") (pin "P1") (pinfunction "VBUS_P1") (pintype "power_in"))
    )
    (net (code "56") (name "Net-(LED1-PadA)") (class "Default")
      (node (ref "LED1") (pin "A") (pinfunction "A_A") (pintype "passive"))
      (node (ref "LED1.1") (pin "A") (pinfunction "A_A") (pintype "passive"))
      (node (ref "R8") (pin "2") (pinfunction "2_2") (pintype "passive"))
      (node (ref "R8.1") (pin "2") (pinfunction "2_2") (pintype "passive"))
    )
    (net (code "57") (name "Net-(LED1.3-PadA)") (class "Default")
      (node (ref "LED1.3") (pin "A") (pinfunction "A_A") (pintype "passive"))
      (node (ref "R13") (pin "2") (pinfunction "2_2") (pintype "passive"))
    )
    (net (code "58") (name "Net-(LED2-PadA)") (class "Default")
      (node (ref "LED2") (pin "A") (pinfunction "A_A") (pintype "passive"))
      (node (ref "LED2.1") (pin "A") (pinfunction "A_A") (pintype "passive"))
      (node (ref "R9") (pin "2") (pinfunction "2_2") (pintype "passive"))
      (node (ref "R9.1") (pin "2") (pinfunction "2_2") (pintype "passive"))
    )
    (net (code "59") (name "Net-(LED3-PadA)") (class "Default")
      (node (ref "LED3") (pin "A") (pinfunction "A_A") (pintype "passive"))
      (node (ref "LED3.1") (pin "A") (pinfunction "A_A") (pintype "passive"))
      (node (ref "R10") (pin "2") (pinfunction "2_2") (pintype "passive"))
      (node (ref "R10.1") (pin "2") (pinfunction "2_2") (pintype "passive"))
    )
    (net (code "60") (name "Net-(LED4-PadA)") (class "Default")
      (node (ref "LED4") (pin "A") (pinfunction "A_A") (pintype "passive"))
      (node (ref "LED4.1") (pin "A") (pinfunction "A_A") (pintype "passive"))
      (node (ref "R11") (pin "1") (pinfunction "1_1") (pintype "passive"))
      (node (ref "R11.1") (pin "2") (pinfunction "2_2") (pintype "passive"))
    )
    (net (code "61") (name "Net-(R1-Pad2)") (class "Default")
      (node (ref "R1") (pin "2") (pinfunction "2_2") (pintype "passive"))
      (node (ref "RX") (pin "A") (pinfunction "A_A") (pintype "passive"))
    )
    (net (code "62") (name "Net-(R22-Pad2)") (class "Default")
      (node (ref "R22") (pin "2") (pinfunction "2_2") (pintype "passive"))
      (node (ref "RED") (pin "A") (pinfunction "A_A") (pintype "passive"))
    )
    (net (code "63") (name "Net-(S7-O)") (class "Default")
      (node (ref "D1") (pin "C") (pinfunction "C_C") (pintype "passive"))
      (node (ref "D2") (pin "C") (pinfunction "C_C") (pintype "passive"))
      (node (ref "F1") (pin "2") (pinfunction "2_2") (pintype "passive"))
      (node (ref "F1.1") (pin "2") (pinfunction "2_2") (pintype "passive"))
      (node (ref "S7") (pin "P$2") (pinfunction "O_P$2") (pintype "passive"))
    )
    (net (code "64") (name "Net-(SG1-1)") (class "Default")
      (node (ref "JP1") (pin "1") (pinfunction "1_1") (pintype "passive"))
      (node (ref "SG1") (pin "+") (pinfunction "1_+") (pintype "passive"))
    )
    (net (code "65") (name "Net-(U1-RTS)") (class "Default")
      (node (ref "C5") (pin "2") (pinfunction "2_2") (pintype "passive"))
      (node (ref "U1") (pin "4") (pinfunction "RTS_4") (pintype "output"))
    )
    (net (code "66") (name "Net-(U1-RX)") (class "Default")
      (node (ref "R5") (pin "2") (pinfunction "2_2") (pintype "passive"))
      (node (ref "U1") (pin "9") (pinfunction "RX_9") (pintype "input"))
    )
    (net (code "67") (name "Net-(U1-TNOW)") (class "Default")
      (node (ref "R1") (pin "1") (pinfunction "1_1") (pintype "passive"))
      (node (ref "U1") (pin "6") (pinfunction "TNOW_6") (pintype "output"))
    )
    (net (code "68") (name "Net-(U1-TX)") (class "Default")
      (node (ref "R3") (pin "2") (pinfunction "2_2") (pintype "passive"))
      (node (ref "U1") (pin "8") (pinfunction "TX_8") (pintype "output"))
    )
    (net (code "69") (name "unconnected-(J2-ID-PadP4)") (class "Default")
      (node (ref "J2") (pin "P4") (pinfunction "ID_P4") (pintype "bidirectional"))
    )
    (net (code "70") (name "unconnected-(S7-P$1-PadP$4)") (class "Default")
      (node (ref "S7") (pin "P$4") (pinfunction "P$1_P$4") (pintype "passive"))
    )
    (net (code "71") (name "unconnected-(S7-P$2-PadP$5)") (class "Default")
      (node (ref "S7") (pin "P$5") (pinfunction "P$2_P$5") (pintype "bidirectional"))
    )
    (net (code "72") (name "unconnected-(U1-CTS-Pad5)") (class "Default")
      (node (ref "U1") (pin "5") (pinfunction "CTS_5") (pintype "input"))
    )
  )
)
